# BOOT_JTAG_AUX.net
KiCad netlist of a schematic drawn in Altium Designer
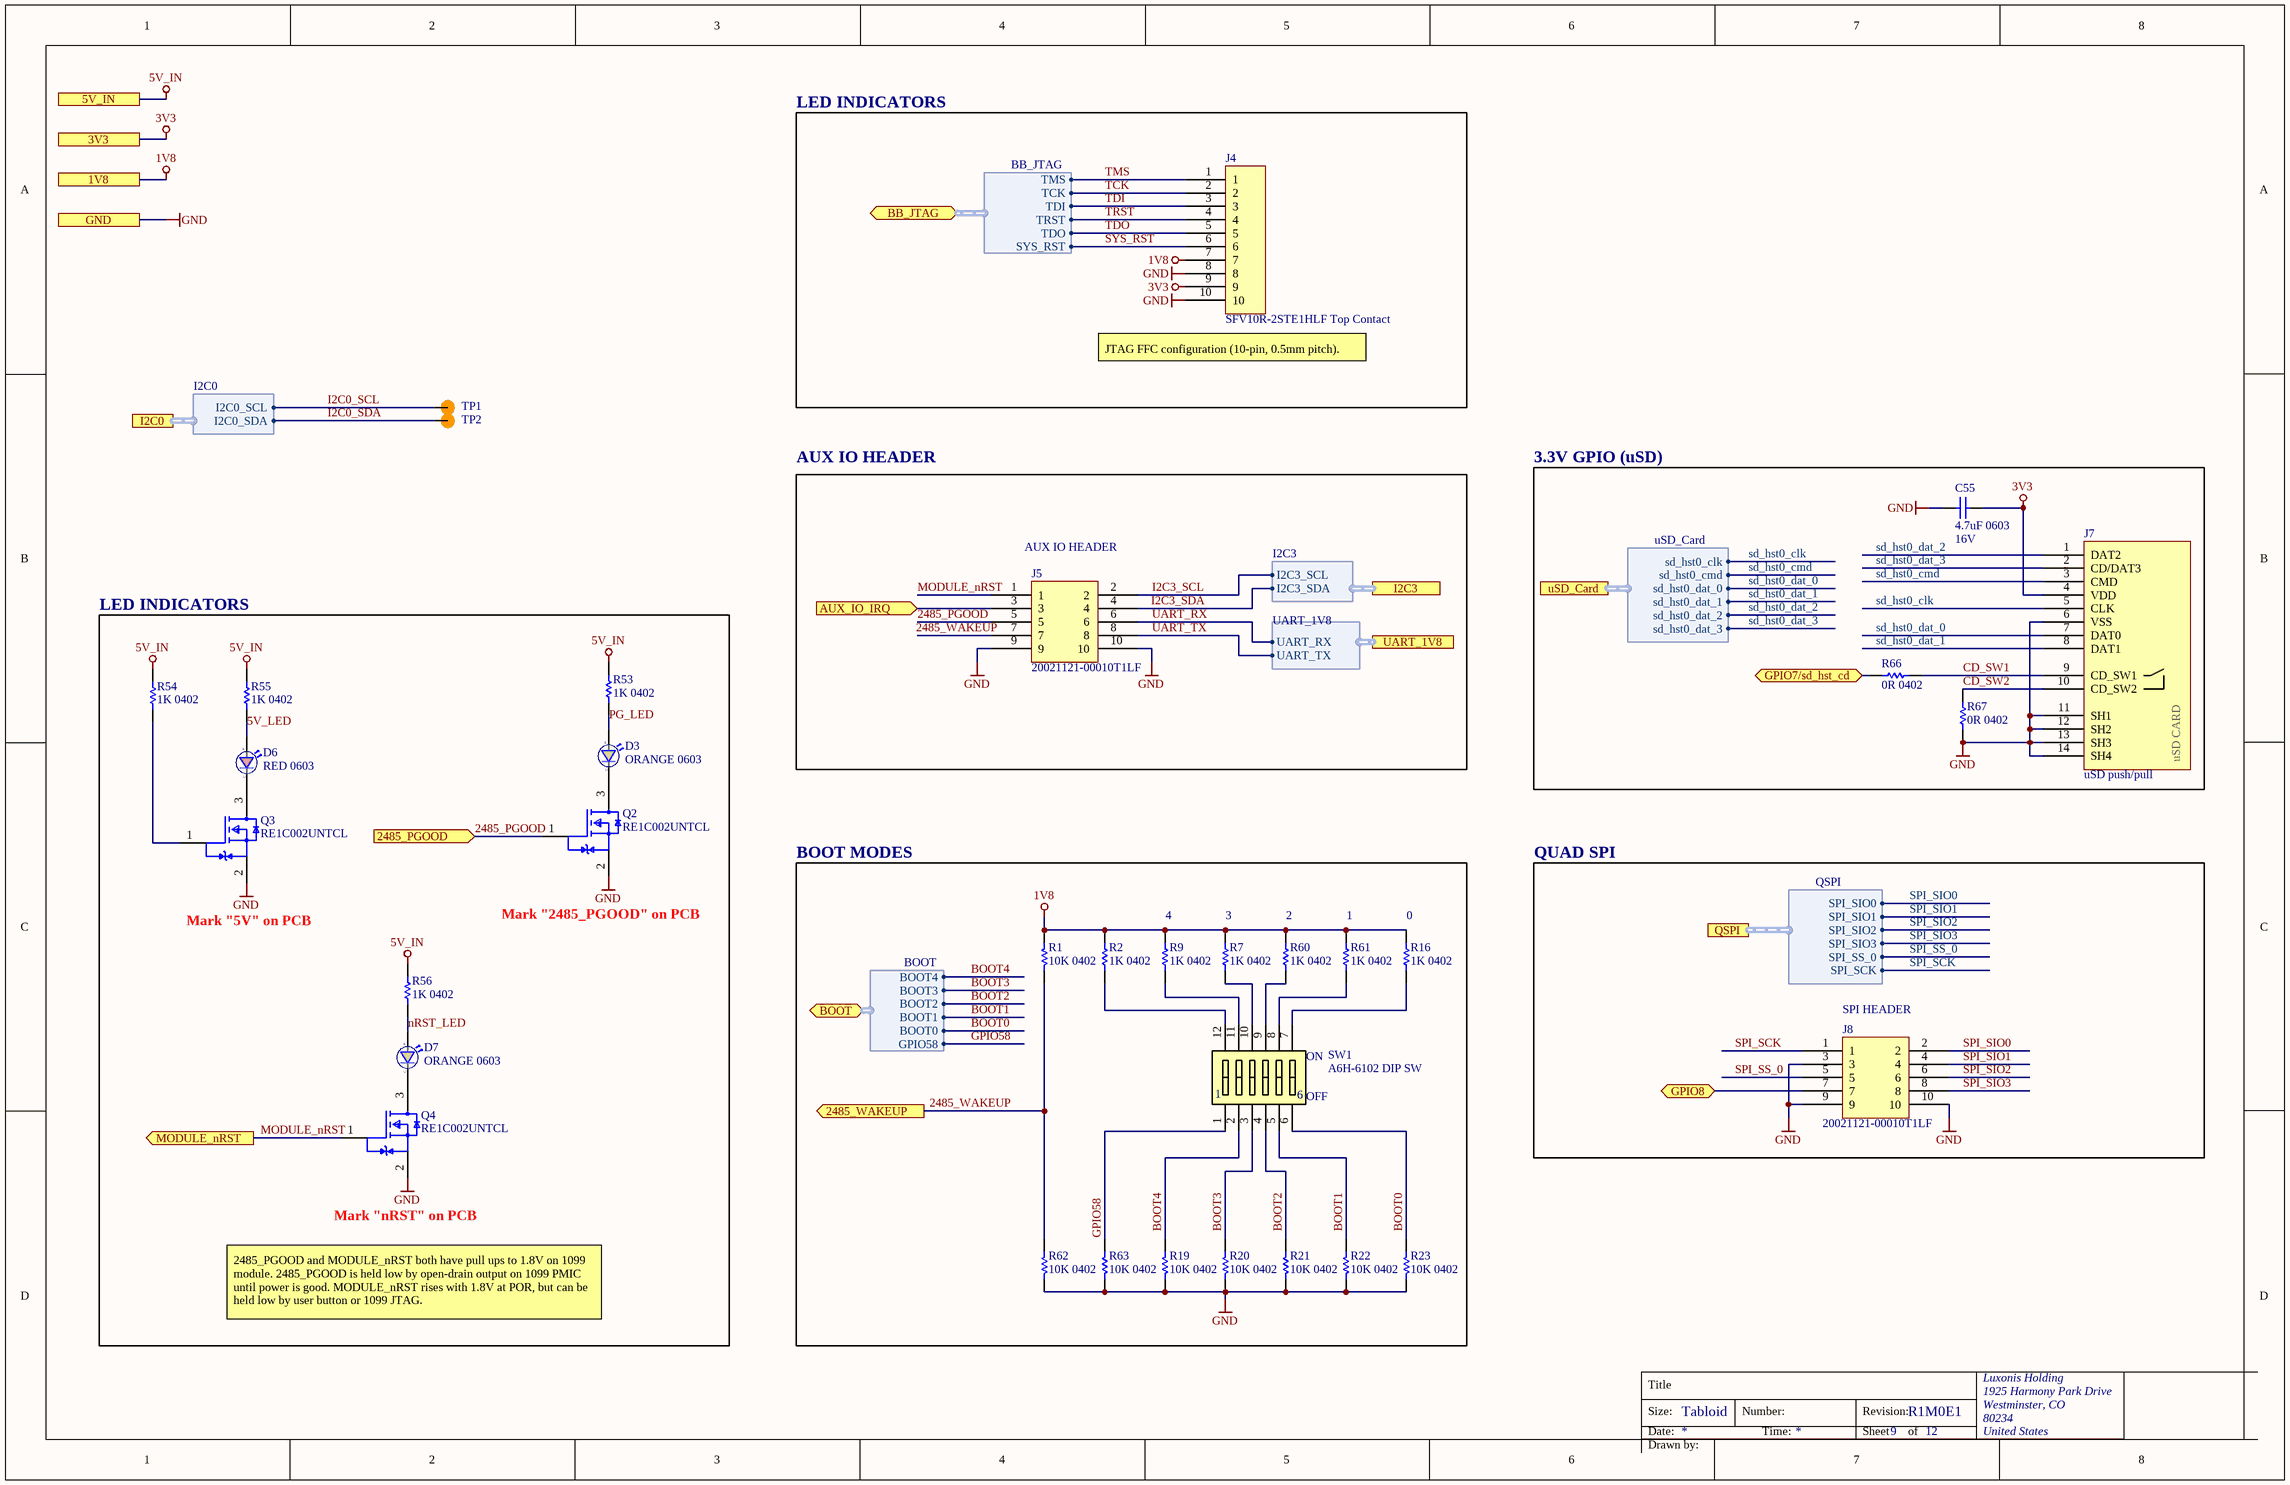
[diagram p0: BOOT_JTAG_AUX.SchDoc]

(export (version "E")
  (design (tool "Eeschema 10.0.6"))
  (components
    (comp (ref "C55")
      (value "4.7uF 0603")
      (footprint "CAP_Altium_Vault_Generic:CAPC0603(1608)100_N")
      (description "CAP CER 4.7UF 16V X5R 0603 10%")
      (fields (field (name "TOLERANCE") "10%") (field (name "VOLTAGE RATING") "16V"))
      (libsource (lib "LuxonisMaster") (part "GRM188R61C475KAAJD"))
    )
    (comp (ref "D3")
      (value "ORANGE 0603")
      (footprint "LuxonisMaster:SML_D1xx8W")
      (description "LED ORANGE DIFFUSED 0603 SMD Orange 605nm LED Indication - Discrete 2.2V 0603 (1608 Metric)")
      (libsource (lib "LuxonisMaster") (part "SML-D12D8WT86"))
    )
    (comp (ref "D6")
      (value "RED 0603")
      (footprint "LuxonisMaster:SML_D1xx8W")
      (description "LED RED DIFFUSED 0603 SMD Red 620nm LED Indication - Discrete 2.2V 0603 (1608 Metric)")
      (libsource (lib "LuxonisMaster") (part "SML-D12U8WT86"))
    )
    (comp (ref "D7")
      (value "ORANGE 0603")
      (footprint "LuxonisMaster:SML_D1xx8W")
      (description "LED ORANGE DIFFUSED 0603 SMD Orange 605nm LED Indication - Discrete 2.2V 0603 (1608 Metric)")
      (libsource (lib "LuxonisMaster") (part "SML-D12D8WT86"))
    )
    (comp (ref "J4")
      (value "SFV10R-2STE1HLF Top Contact")
      (footprint "LuxonisMaster:SFV10R-2STE1HLF")
      (description "CONN FFC TOP 10POS 0.50MM R/A")
      (libsource (lib "LuxonisMaster") (part "SFV10R-2STE1HLF"))
    )
    (comp (ref "J5")
      (value "20021121-00010T1LF")
      (footprint "LuxonisMaster:20021121-00010T1LF")
      (description "CONN HEADER SMD 10POS 1.27MM")
      (libsource (lib "LuxonisMaster") (part "20021121-00010T1LF"))
    )
    (comp (ref "J7")
      (value "uSD push/pull")
      (footprint "LuxonisMaster:104031-0811")
      (description "CONN MICRO SD CARD PUSH-PULL R/A")
      (libsource (lib "LuxonisMaster") (part "104031-0811"))
    )
    (comp (ref "J8")
      (value "20021121-00010T1LF")
      (footprint "LuxonisMaster:20021121-00010T1LF")
      (description "CONN HEADER SMD 10POS 1.27MM")
      (libsource (lib "LuxonisMaster") (part "20021121-00010T1LF"))
    )
    (comp (ref "Q2")
      (value "RE1C002UNTCL")
      (footprint "LuxonisMaster:RE1C002UNTCL")
      (description "MOSFET N-CH 20V 0.2A EMT3")
      (libsource (lib "LuxonisMaster") (part "RE1C002UNTCL"))
    )
    (comp (ref "Q3")
      (value "RE1C002UNTCL")
      (footprint "LuxonisMaster:RE1C002UNTCL")
      (description "MOSFET N-CH 20V 0.2A EMT3")
      (libsource (lib "LuxonisMaster") (part "RE1C002UNTCL"))
    )
    (comp (ref "Q4")
      (value "RE1C002UNTCL")
      (footprint "LuxonisMaster:RE1C002UNTCL")
      (description "MOSFET N-CH 20V 0.2A EMT3")
      (libsource (lib "LuxonisMaster") (part "RE1C002UNTCL"))
    )
    (comp (ref "R1")
      (value "10K 0402")
      (footprint "RES_Altium_Vault_Generic:RESC0402(1005)_N")
      (fields (field (name "TOLERANCE") "1%"))
      (libsource (lib "LuxonisMaster") (part "RC0402FR-1310KL"))
    )
    (comp (ref "R2")
      (value "1K 0402")
      (footprint "RES_Altium_Vault_Generic:RESC0402(1005)_N")
      (fields (field (name "TOLERANCE") "1%"))
      (libsource (lib "LuxonisMaster") (part "RC0402FR-071KL"))
    )
    (comp (ref "R7")
      (value "1K 0402")
      (footprint "RES_Altium_Vault_Generic:RESC0402(1005)_N")
      (fields (field (name "TOLERANCE") "1%"))
      (libsource (lib "LuxonisMaster") (part "RC0402FR-071KL"))
    )
    (comp (ref "R9")
      (value "1K 0402")
      (footprint "RES_Altium_Vault_Generic:RESC0402(1005)_N")
      (fields (field (name "TOLERANCE") "1%"))
      (libsource (lib "LuxonisMaster") (part "RC0402FR-071KL"))
    )
    (comp (ref "R16")
      (value "1K 0402")
      (footprint "RES_Altium_Vault_Generic:RESC0402(1005)_N")
      (fields (field (name "TOLERANCE") "1%"))
      (libsource (lib "LuxonisMaster") (part "RC0402FR-071KL"))
    )
    (comp (ref "R19")
      (value "10K 0402")
      (footprint "RES_Altium_Vault_Generic:RESC0402(1005)_N")
      (fields (field (name "TOLERANCE") "1%"))
      (libsource (lib "LuxonisMaster") (part "RC0402FR-1310KL"))
    )
    (comp (ref "R20")
      (value "10K 0402")
      (footprint "RES_Altium_Vault_Generic:RESC0402(1005)_N")
      (fields (field (name "TOLERANCE") "1%"))
      (libsource (lib "LuxonisMaster") (part "RC0402FR-1310KL"))
    )
    (comp (ref "R21")
      (value "10K 0402")
      (footprint "RES_Altium_Vault_Generic:RESC0402(1005)_N")
      (fields (field (name "TOLERANCE") "1%"))
      (libsource (lib "LuxonisMaster") (part "RC0402FR-1310KL"))
    )
    (comp (ref "R22")
      (value "10K 0402")
      (footprint "RES_Altium_Vault_Generic:RESC0402(1005)_N")
      (fields (field (name "TOLERANCE") "1%"))
      (libsource (lib "LuxonisMaster") (part "RC0402FR-1310KL"))
    )
    (comp (ref "R23")
      (value "10K 0402")
      (footprint "RES_Altium_Vault_Generic:RESC0402(1005)_N")
      (fields (field (name "TOLERANCE") "1%"))
      (libsource (lib "LuxonisMaster") (part "RC0402FR-1310KL"))
    )
    (comp (ref "R53")
      (value "1K 0402")
      (footprint "RES_Altium_Vault_Generic:RESC0402(1005)_N")
      (fields (field (name "TOLERANCE") "1%"))
      (libsource (lib "LuxonisMaster") (part "RC0402FR-071KL"))
    )
    (comp (ref "R54")
      (value "1K 0402")
      (footprint "RES_Altium_Vault_Generic:RESC0402(1005)_N")
      (fields (field (name "TOLERANCE") "1%"))
      (libsource (lib "LuxonisMaster") (part "RC0402FR-071KL"))
    )
    (comp (ref "R55")
      (value "1K 0402")
      (footprint "RES_Altium_Vault_Generic:RESC0402(1005)_N")
      (fields (field (name "TOLERANCE") "1%"))
      (libsource (lib "LuxonisMaster") (part "RC0402FR-071KL"))
    )
    (comp (ref "R56")
      (value "1K 0402")
      (footprint "RES_Altium_Vault_Generic:RESC0402(1005)_N")
      (fields (field (name "TOLERANCE") "1%"))
      (libsource (lib "LuxonisMaster") (part "RC0402FR-071KL"))
    )
    (comp (ref "R60")
      (value "1K 0402")
      (footprint "RES_Altium_Vault_Generic:RESC0402(1005)_N")
      (fields (field (name "TOLERANCE") "1%"))
      (libsource (lib "LuxonisMaster") (part "RC0402FR-071KL"))
    )
    (comp (ref "R61")
      (value "1K 0402")
      (footprint "RES_Altium_Vault_Generic:RESC0402(1005)_N")
      (fields (field (name "TOLERANCE") "1%"))
      (libsource (lib "LuxonisMaster") (part "RC0402FR-071KL"))
    )
    (comp (ref "R62")
      (value "10K 0402")
      (footprint "RES_Altium_Vault_Generic:RESC0402(1005)_N")
      (fields (field (name "TOLERANCE") "1%"))
      (libsource (lib "LuxonisMaster") (part "RC0402FR-1310KL"))
    )
    (comp (ref "R63")
      (value "10K 0402")
      (footprint "RES_Altium_Vault_Generic:RESC0402(1005)_N")
      (fields (field (name "TOLERANCE") "1%"))
      (libsource (lib "LuxonisMaster") (part "RC0402FR-1310KL"))
    )
    (comp (ref "R66")
      (value "0R 0402")
      (footprint "RES_Altium_Vault_Generic:RESC0402(1005)_N")
      (description "RES SMD 0 OHM JUMPER 1/16W 0402")
      (fields (field (name "TOLERANCE") "5%"))
      (libsource (lib "LuxonisMaster") (part "CRCW04020000Z0ED"))
    )
    (comp (ref "R67")
      (value "0R 0402")
      (footprint "RES_Altium_Vault_Generic:RESC0402(1005)_N")
      (description "RES SMD 0 OHM JUMPER 1/16W 0402")
      (fields (field (name "TOLERANCE") "5%"))
      (libsource (lib "LuxonisMaster") (part "CRCW04020000Z0ED"))
    )
    (comp (ref "SW1")
      (value "A6H-6102 DIP SW")
      (footprint "LuxonisMaster:A6H-610x")
      (description "SWITCH SLIDE DIP SPST 25MA 24V (SEALED)")
      (libsource (lib "LuxonisMaster") (part "A6H-6102"))
    )
    (comp (ref "TP1")
      (value "TP100_200_NS")
      (footprint "LuxonisMaster:TP100_200_NS")
      (libsource (lib "LuxonisMaster") (part "TEST_POINT"))
    )
    (comp (ref "TP2")
      (value "TP100_200_NS")
      (footprint "LuxonisMaster:TP100_200_NS")
      (libsource (lib "LuxonisMaster") (part "TEST_POINT"))
    )
  )
  (nets
    (net (code "8") (name "/5V_LED") (class "Default")
      (node (ref "D6") (pin "2") (pinfunction "A_2") (pintype "passive"))
      (node (ref "R55") (pin "1") (pinfunction "1_1") (pintype "passive"))
    )
    (net (code "9") (name "/2485_PGOOD") (class "Default")
      (node (ref "J5") (pin "5") (pinfunction "5_5") (pintype "passive"))
      (node (ref "Q2") (pin "1") (pinfunction "Gate_1") (pintype "passive"))
    )
    (net (code "10") (name "/2485_WAKEUP") (class "Default")
      (node (ref "R1") (pin "2") (pinfunction "2_2") (pintype "passive"))
      (node (ref "R62") (pin "1") (pinfunction "1_1") (pintype "passive"))
    )
    (net (code "11") (name "/AUX_IO_IRQ") (class "Default")
      (node (ref "J5") (pin "3") (pinfunction "3_3") (pintype "passive"))
    )
    (net (code "12") (name "/BOOT0") (class "Default")
      (node (ref "R23") (pin "1") (pinfunction "1_1") (pintype "passive"))
      (node (ref "SW1") (pin "6") (pinfunction "6_6") (pintype "passive"))
    )
    (net (code "13") (name "/BOOT1") (class "Default")
      (node (ref "R22") (pin "1") (pinfunction "1_1") (pintype "passive"))
      (node (ref "SW1") (pin "5") (pinfunction "5_5") (pintype "passive"))
    )
    (net (code "14") (name "/BOOT2") (class "Default")
      (node (ref "R21") (pin "1") (pinfunction "1_1") (pintype "passive"))
      (node (ref "SW1") (pin "4") (pinfunction "4_4") (pintype "passive"))
    )
    (net (code "15") (name "/BOOT3") (class "Default")
      (node (ref "R20") (pin "1") (pinfunction "1_1") (pintype "passive"))
      (node (ref "SW1") (pin "3") (pinfunction "3_3") (pintype "passive"))
    )
    (net (code "16") (name "/BOOT4") (class "Default")
      (node (ref "R19") (pin "1") (pinfunction "1_1") (pintype "passive"))
      (node (ref "SW1") (pin "2") (pinfunction "2_2") (pintype "passive"))
    )
    (net (code "17") (name "/CD_SW1") (class "Default")
      (node (ref "J7") (pin "9") (pinfunction "CD_SW1_9") (pintype "passive"))
      (node (ref "R66") (pin "1") (pinfunction "1_1") (pintype "passive"))
    )
    (net (code "18") (name "/CD_SW2") (class "Default")
      (node (ref "J7") (pin "10") (pinfunction "CD_SW2_10") (pintype "passive"))
      (node (ref "R67") (pin "2") (pinfunction "2_2") (pintype "passive"))
    )
    (net (code "19") (name "/GPIO7{slash}sd_hst_cd") (class "Default")
      (node (ref "R66") (pin "2") (pinfunction "2_2") (pintype "passive"))
    )
    (net (code "20") (name "/GPIO8") (class "Default")
      (node (ref "J8") (pin "7") (pinfunction "7_7") (pintype "passive"))
    )
    (net (code "21") (name "/GPIO58") (class "Default")
      (node (ref "R63") (pin "1") (pinfunction "1_1") (pintype "passive"))
      (node (ref "SW1") (pin "1") (pinfunction "1_1") (pintype "passive"))
    )
    (net (code "22") (name "/I2C0_SCL") (class "Default") (node (ref "TP1") (pin "1") (pintype "passive")))
    (net (code "23") (name "/I2C0_SDA") (class "Default") (node (ref "TP2") (pin "1") (pintype "passive")))
    (net (code "24") (name "/I2C3_SCL") (class "Default")
      (node (ref "J5") (pin "2") (pinfunction "2_2") (pintype "passive"))
    )
    (net (code "25") (name "/I2C3_SDA") (class "Default")
      (node (ref "J5") (pin "4") (pinfunction "4_4") (pintype "passive"))
    )
    (net (code "26") (name "/MODULE_nRST") (class "Default")
      (node (ref "J5") (pin "1") (pinfunction "1_1") (pintype "passive"))
      (node (ref "Q4") (pin "1") (pinfunction "Gate_1") (pintype "passive"))
    )
    (net (code "27") (name "/PG_LED") (class "Default")
      (node (ref "D3") (pin "2") (pinfunction "A_2") (pintype "passive"))
      (node (ref "R53") (pin "1") (pinfunction "1_1") (pintype "passive"))
    )
    (net (code "28") (name "/SPI_SCK") (class "Default")
      (node (ref "J8") (pin "1") (pinfunction "1_1") (pintype "passive"))
    )
    (net (code "29") (name "/SPI_SIO0") (class "Default")
      (node (ref "J8") (pin "2") (pinfunction "2_2") (pintype "passive"))
    )
    (net (code "30") (name "/SPI_SIO1") (class "Default")
      (node (ref "J8") (pin "4") (pinfunction "4_4") (pintype "passive"))
    )
    (net (code "31") (name "/SPI_SIO2") (class "Default")
      (node (ref "J8") (pin "6") (pinfunction "6_6") (pintype "passive"))
    )
    (net (code "32") (name "/SPI_SIO3") (class "Default")
      (node (ref "J8") (pin "8") (pinfunction "8_8") (pintype "passive"))
    )
    (net (code "33") (name "/SPI_SS_0") (class "Default")
      (node (ref "J8") (pin "5") (pinfunction "5_5") (pintype "passive"))
    )
    (net (code "34") (name "/SYS_RST") (class "Default")
      (node (ref "J4") (pin "6") (pinfunction "6_6") (pintype "passive"))
    )
    (net (code "35") (name "/TCK") (class "Default")
      (node (ref "J4") (pin "2") (pinfunction "2_2") (pintype "passive"))
    )
    (net (code "36") (name "/TDI") (class "Default")
      (node (ref "J4") (pin "3") (pinfunction "3_3") (pintype "passive"))
    )
    (net (code "37") (name "/TDO") (class "Default")
      (node (ref "J4") (pin "5") (pinfunction "5_5") (pintype "passive"))
    )
    (net (code "38") (name "/TMS") (class "Default")
      (node (ref "J4") (pin "1") (pinfunction "1_1") (pintype "passive"))
    )
    (net (code "39") (name "/TRST") (class "Default")
      (node (ref "J4") (pin "4") (pinfunction "4_4") (pintype "passive"))
    )
    (net (code "40") (name "/UART_RX") (class "Default")
      (node (ref "J5") (pin "6") (pinfunction "6_6") (pintype "passive"))
    )
    (net (code "41") (name "/UART_TX") (class "Default")
      (node (ref "J5") (pin "8") (pinfunction "8_8") (pintype "passive"))
    )
    (net (code "42") (name "/nRST_LED") (class "Default")
      (node (ref "D7") (pin "2") (pinfunction "A_2") (pintype "passive"))
      (node (ref "R56") (pin "1") (pinfunction "1_1") (pintype "passive"))
    )
    (net (code "43") (name "/sd_hst0_clk") (class "Default")
      (node (ref "J7") (pin "5") (pinfunction "CLK_5") (pintype "passive"))
    )
    (net (code "44") (name "/sd_hst0_cmd") (class "Default")
      (node (ref "J7") (pin "3") (pinfunction "CMD_3") (pintype "passive"))
    )
    (net (code "45") (name "/sd_hst0_dat_0") (class "Default")
      (node (ref "J7") (pin "7") (pinfunction "DAT0_7") (pintype "passive"))
    )
    (net (code "46") (name "/sd_hst0_dat_1") (class "Default")
      (node (ref "J7") (pin "8") (pinfunction "DAT1_8") (pintype "passive"))
    )
    (net (code "47") (name "/sd_hst0_dat_2") (class "Default")
      (node (ref "J7") (pin "1") (pinfunction "DAT2_1") (pintype "passive"))
    )
    (net (code "48") (name "/sd_hst0_dat_3") (class "Default")
      (node (ref "J7") (pin "2") (pinfunction "CD/DAT3_2") (pintype "passive"))
    )
    (net (code "56") (name "1V8") (class "Default")
      (node (ref "J4") (pin "7") (pinfunction "7_7") (pintype "passive"))
      (node (ref "R1") (pin "1") (pinfunction "1_1") (pintype "passive"))
      (node (ref "R16") (pin "2") (pinfunction "2_2") (pintype "passive"))
      (node (ref "R2") (pin "2") (pinfunction "2_2") (pintype "passive"))
      (node (ref "R60") (pin "2") (pinfunction "2_2") (pintype "passive"))
      (node (ref "R61") (pin "2") (pinfunction "2_2") (pintype "passive"))
      (node (ref "R7") (pin "2") (pinfunction "2_2") (pintype "passive"))
      (node (ref "R9") (pin "2") (pinfunction "2_2") (pintype "passive"))
    )
    (net (code "57") (name "3V3") (class "Default")
      (node (ref "C55") (pin "2") (pinfunction "2_2") (pintype "passive"))
      (node (ref "J4") (pin "9") (pinfunction "9_9") (pintype "passive"))
      (node (ref "J7") (pin "4") (pinfunction "VDD_4") (pintype "passive"))
    )
    (net (code "58") (name "5V_IN") (class "Default")
      (node (ref "R53") (pin "2") (pinfunction "2_2") (pintype "passive"))
      (node (ref "R54") (pin "2") (pinfunction "2_2") (pintype "passive"))
      (node (ref "R55") (pin "2") (pinfunction "2_2") (pintype "passive"))
      (node (ref "R56") (pin "2") (pinfunction "2_2") (pintype "passive"))
    )
    (net (code "59") (name "GND") (class "Default")
      (node (ref "C55") (pin "1") (pinfunction "1_1") (pintype "passive"))
      (node (ref "J4") (pin "10") (pinfunction "10_10") (pintype "passive"))
      (node (ref "J4") (pin "8") (pinfunction "8_8") (pintype "passive"))
      (node (ref "J5") (pin "10") (pinfunction "10_10") (pintype "passive"))
      (node (ref "J5") (pin "9") (pinfunction "9_9") (pintype "passive"))
      (node (ref "J7") (pin "11") (pinfunction "SH1_11") (pintype "passive"))
      (node (ref "J7") (pin "12") (pinfunction "SH2_12") (pintype "passive"))
      (node (ref "J7") (pin "13") (pinfunction "SH3_13") (pintype "passive"))
      (node (ref "J7") (pin "14") (pinfunction "SH4_14") (pintype "passive"))
      (node (ref "J7") (pin "6") (pinfunction "VSS_6") (pintype "passive"))
      (node (ref "J8") (pin "10") (pinfunction "10_10") (pintype "passive"))
      (node (ref "J8") (pin "3") (pinfunction "3_3") (pintype "passive"))
      (node (ref "J8") (pin "9") (pinfunction "9_9") (pintype "passive"))
      (node (ref "Q2") (pin "2") (pinfunction "Source_2") (pintype "passive"))
      (node (ref "Q3") (pin "2") (pinfunction "Source_2") (pintype "passive"))
      (node (ref "Q4") (pin "2") (pinfunction "Source_2") (pintype "passive"))
      (node (ref "R19") (pin "2") (pinfunction "2_2") (pintype "passive"))
      (node (ref "R20") (pin "2") (pinfunction "2_2") (pintype "passive"))
      (node (ref "R21") (pin "2") (pinfunction "2_2") (pintype "passive"))
      (node (ref "R22") (pin "2") (pinfunction "2_2") (pintype "passive"))
      (node (ref "R23") (pin "2") (pinfunction "2_2") (pintype "passive"))
      (node (ref "R62") (pin "2") (pinfunction "2_2") (pintype "passive"))
      (node (ref "R63") (pin "2") (pinfunction "2_2") (pintype "passive"))
      (node (ref "R67") (pin "1") (pinfunction "1_1") (pintype "passive"))
    )
    (net (code "60") (name "Net-(D3-C)") (class "Default")
      (node (ref "D3") (pin "1") (pinfunction "C_1") (pintype "passive"))
      (node (ref "Q2") (pin "3") (pinfunction "Drain_3") (pintype "passive"))
    )
    (net (code "61") (name "Net-(D6-C)") (class "Default")
      (node (ref "D6") (pin "1") (pinfunction "C_1") (pintype "passive"))
      (node (ref "Q3") (pin "3") (pinfunction "Drain_3") (pintype "passive"))
    )
    (net (code "62") (name "Net-(D7-C)") (class "Default")
      (node (ref "D7") (pin "1") (pinfunction "C_1") (pintype "passive"))
      (node (ref "Q4") (pin "3") (pinfunction "Drain_3") (pintype "passive"))
    )
    (net (code "63") (name "Net-(Q3-Gate)") (class "Default")
      (node (ref "Q3") (pin "1") (pinfunction "Gate_1") (pintype "passive"))
      (node (ref "R54") (pin "1") (pinfunction "1_1") (pintype "passive"))
    )
    (net (code "64") (name "Net-(R2-Pad1)") (class "Default")
      (node (ref "R2") (pin "1") (pinfunction "1_1") (pintype "passive"))
      (node (ref "SW1") (pin "12") (pinfunction "12_12") (pintype "passive"))
    )
    (net (code "65") (name "Net-(R7-Pad1)") (class "Default")
      (node (ref "R7") (pin "1") (pinfunction "1_1") (pintype "passive"))
      (node (ref "SW1") (pin "10") (pinfunction "10_10") (pintype "passive"))
    )
    (net (code "66") (name "Net-(R9-Pad1)") (class "Default")
      (node (ref "R9") (pin "1") (pinfunction "1_1") (pintype "passive"))
      (node (ref "SW1") (pin "11") (pinfunction "11_11") (pintype "passive"))
    )
    (net (code "67") (name "Net-(R16-Pad1)") (class "Default")
      (node (ref "R16") (pin "1") (pinfunction "1_1") (pintype "passive"))
      (node (ref "SW1") (pin "7") (pinfunction "7_7") (pintype "passive"))
    )
    (net (code "68") (name "Net-(R60-Pad1)") (class "Default")
      (node (ref "R60") (pin "1") (pinfunction "1_1") (pintype "passive"))
      (node (ref "SW1") (pin "9") (pinfunction "9_9") (pintype "passive"))
    )
    (net (code "69") (name "Net-(R61-Pad1)") (class "Default")
      (node (ref "R61") (pin "1") (pinfunction "1_1") (pintype "passive"))
      (node (ref "SW1") (pin "8") (pinfunction "8_8") (pintype "passive"))
    )
    (net (code "70") (name "unconnected-(J5-Pad7)") (class "Default")
      (node (ref "J5") (pin "7") (pinfunction "7_7") (pintype "passive"))
    )
  )
)
